# Sheet1.net
KiCad netlist of a schematic drawn in Altium Designer
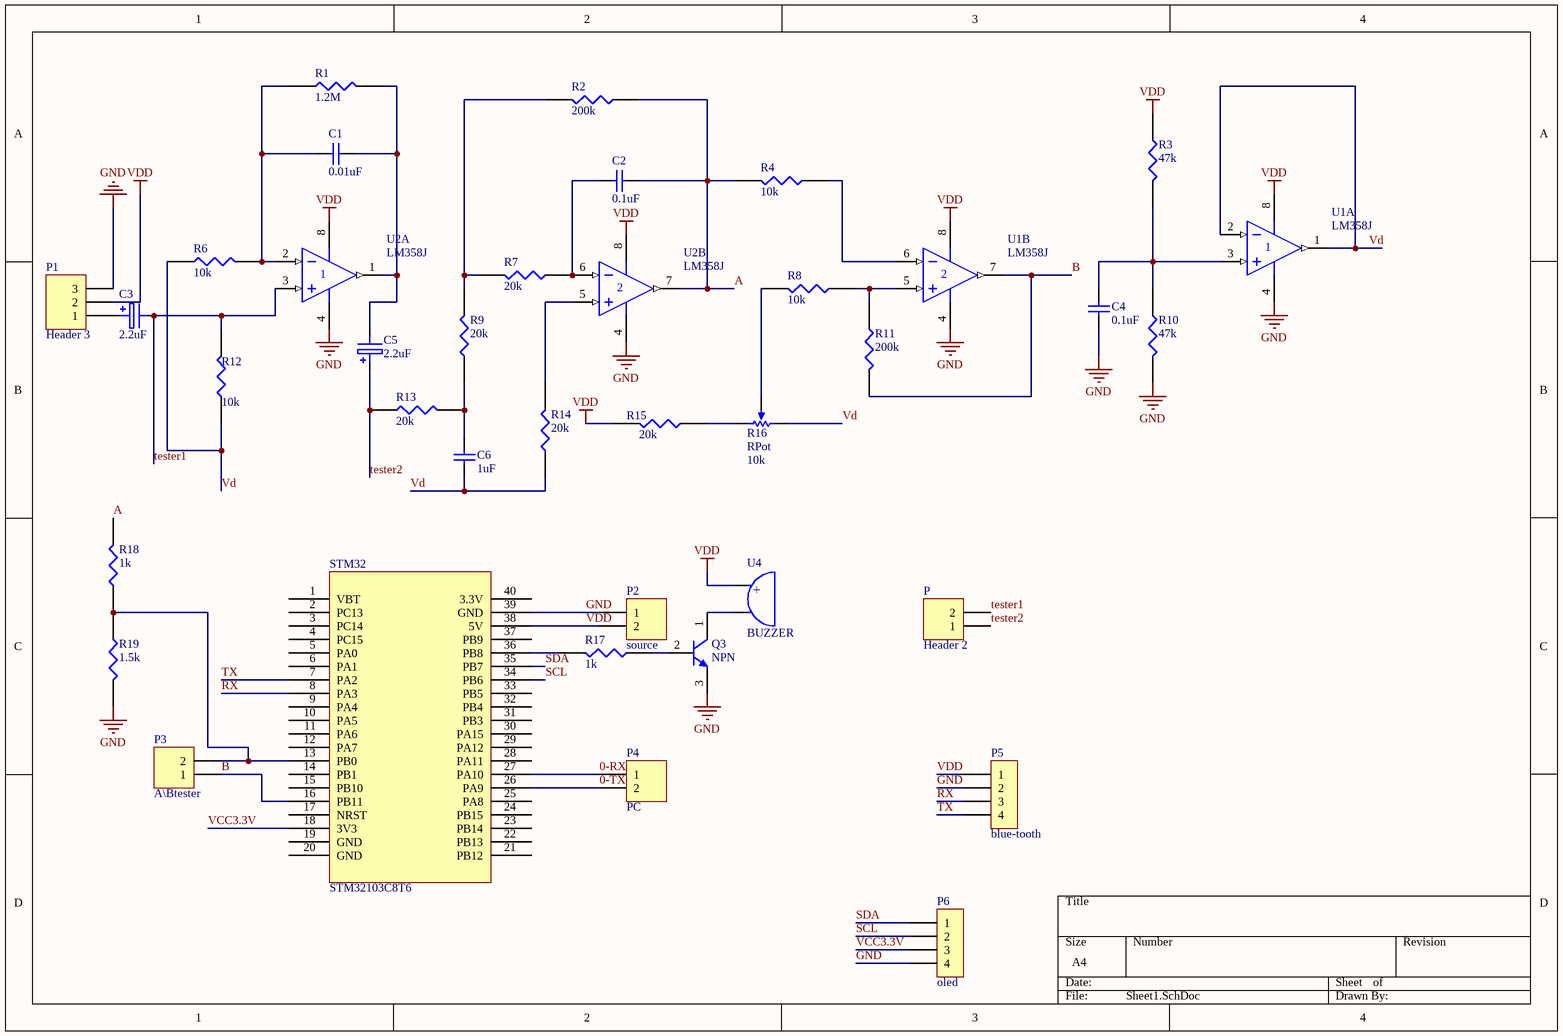
[diagram p0: Sheet1.SchDoc]

(export (version "E")
  (design (tool "Eeschema 10.0.6"))
  (components
    (comp (ref "C1")
      (value "0.01uF")
      (footprint "C2")
      (description "Capacitor")
      (fields (field (name "PUBLISHER") "Altium Limited"))
      (libsource (lib "短学期") (part "Cap"))
    )
    (comp (ref "C2")
      (value "0.1uF")
      (footprint "C2")
      (description "Capacitor")
      (fields (field (name "PUBLISHER") "Altium Limited"))
      (libsource (lib "短学期") (part "Cap"))
    )
    (comp (ref "C3")
      (value "2.2uF")
      (footprint "RB.15/.3")
      (description "电解电容")
      (libsource (lib "Exp20030704") (part "Cap2"))
    )
    (comp (ref "C4")
      (value "0.1uF")
      (footprint "C2")
      (description "Capacitor")
      (fields (field (name "PUBLISHER") "Altium Limited"))
      (libsource (lib "短学期") (part "Cap"))
    )
    (comp (ref "C5")
      (value "2.2uF")
      (footprint "RB.15/.3")
      (description "电解电容")
      (libsource (lib "") (part "Cap2_1"))
    )
    (comp (ref "C6")
      (value "1uF")
      (footprint "C2")
      (description "Capacitor")
      (fields (field (name "PUBLISHER") "Altium Limited"))
      (libsource (lib "短学期") (part "Cap"))
    )
    (comp (ref "P")
      (value "Header 2")
      (footprint "SIP2")
      (description "Header, 2-Pin")
      (fields (field (name "PUBLISHER") "Altium Limited"))
      (libsource (lib "") (part "Header 2_1"))
    )
    (comp (ref "P1")
      (value "Header 3")
      (footprint "SIP3")
      (description "Header, 3-Pin")
      (fields (field (name "PUBLISHER") "Altium Limited"))
      (libsource (lib "短学期") (part "Header 3"))
    )
    (comp (ref "P2")
      (value "source")
      (footprint "SIP2")
      (description "Header, 2-Pin")
      (fields (field (name "PUBLISHER") "Altium Limited"))
      (libsource (lib "Exp20030704") (part "Header 2"))
    )
    (comp (ref "P3")
      (value "~{A}Btester")
      (footprint "SIP2")
      (description "Header, 2-Pin")
      (fields (field (name "PUBLISHER") "Altium Limited"))
      (libsource (lib "") (part "Header 2_1"))
    )
    (comp (ref "P4")
      (value "PC")
      (footprint "SIP2")
      (description "Header, 2-Pin")
      (fields (field (name "PUBLISHER") "Altium Limited"))
      (libsource (lib "Exp20030704") (part "Header 2"))
    )
    (comp (ref "P5")
      (value "blue-tooth")
      (footprint "SIP4")
      (description "Connector")
      (libsource (lib "Exp20030704") (part "Header 4"))
    )
    (comp (ref "P6")
      (value "oled")
      (footprint "SSD1306")
      (description "Connector")
      (libsource (lib "Exp20030704") (part "Header 4"))
    )
    (comp (ref "Q3")
      (value "NPN")
      (footprint "TO-P2")
      (description "NPN Bipolar Transistor")
      (fields (field (name "PUBLISHER") "Altium Limited"))
      (libsource (lib "Exp20030704") (part "NPN"))
    )
    (comp (ref "R1") (value "1.2M") (footprint "AXIAL0.4") (libsource (lib "Exp20030704") (part "RES1")))
    (comp (ref "R2") (value "200k") (footprint "AXIAL0.4") (libsource (lib "Exp20030704") (part "RES1")))
    (comp (ref "R3") (value "47k") (footprint "AXIAL0.4") (libsource (lib "Exp20030704") (part "RES1")))
    (comp (ref "R4") (value "10k") (footprint "AXIAL0.4") (libsource (lib "Exp20030704") (part "RES1")))
    (comp (ref "R6") (value "10k") (footprint "AXIAL0.4") (libsource (lib "Exp20030704") (part "RES1")))
    (comp (ref "R7") (value "20k") (footprint "AXIAL0.4") (libsource (lib "Exp20030704") (part "RES1")))
    (comp (ref "R8") (value "10k") (footprint "AXIAL0.4") (libsource (lib "Exp20030704") (part "RES1")))
    (comp (ref "R9") (value "20k") (footprint "AXIAL0.4") (libsource (lib "Exp20030704") (part "RES1")))
    (comp (ref "R10") (value "47k") (footprint "AXIAL0.4") (libsource (lib "Exp20030704") (part "RES1")))
    (comp (ref "R11") (value "200k") (footprint "AXIAL0.4") (libsource (lib "Exp20030704") (part "RES1")))
    (comp (ref "R12") (value "10k") (footprint "AXIAL0.4") (libsource (lib "Exp20030704") (part "RES1")))
    (comp (ref "R13") (value "20k") (footprint "AXIAL0.4") (libsource (lib "Exp20030704") (part "RES1")))
    (comp (ref "R14") (value "20k") (footprint "AXIAL0.4") (libsource (lib "Exp20030704") (part "RES1")))
    (comp (ref "R15") (value "20k") (footprint "AXIAL0.4") (libsource (lib "Exp20030704") (part "RES1")))
    (comp (ref "R16")
      (value "RPot")
      (footprint "VR5")
      (description "Potentiometer")
      (fields (field (name "ALTIUM_VALUE") "10k") (field (name "PUBLISHER") "Altium Limited"))
      (libsource (lib "Miscellaneous Devices") (part "RPot"))
    )
    (comp (ref "R17") (value "1k") (footprint "AXIAL0.4") (libsource (lib "Exp20030704") (part "RES1")))
    (comp (ref "R18") (value "1k") (footprint "AXIAL0.4") (libsource (lib "Exp20030704") (part "RES1")))
    (comp (ref "R19") (value "1.5k") (footprint "AXIAL0.4") (libsource (lib "Exp20030704") (part "RES1")))
    (comp (ref "STM32")
      (value "STM32103C8T6")
      (footprint "STM32F103C8T6")
      (libsource (lib "Exp20030704") (part "STM32103C8T6"))
    )
    (comp (ref "U1")
      (value "LM358J")
      (footprint "DIP-8")
      (description "Dual Low-Power Operational Amplifier")
      (fields (field (name "PUBLISHER") "Altium Limited"))
      (libsource (lib "Exp20030704") (part "LM358J"))
    )
    (comp (ref "U2")
      (value "LM358J")
      (footprint "DIP-8")
      (description "Dual Low-Power Operational Amplifier")
      (fields (field (name "PUBLISHER") "Altium Limited"))
      (libsource (lib "Exp20030704") (part "LM358J"))
    )
    (comp (ref "U4")
      (value "BUZZER")
      (footprint "Buzzer")
      (description "Buzzer")
      (libsource (lib "Miscellaneous Devices") (part "BUZZER"))
    )
  )
  (nets
    (net (code "1") (name "/0-RX") (class "Default")
      (node (ref "P4") (pin "1") (pinfunction "1_1") (pintype "passive"))
      (node (ref "STM32") (pin "27") (pinfunction "PA10_27") (pintype "passive"))
    )
    (net (code "2") (name "/0-TX") (class "Default")
      (node (ref "P4") (pin "2") (pinfunction "2_2") (pintype "passive"))
      (node (ref "STM32") (pin "26") (pinfunction "PA9_26") (pintype "passive"))
    )
    (net (code "3") (name "/A") (class "Default")
      (node (ref "C2") (pin "2") (pinfunction "2_2") (pintype "passive"))
      (node (ref "R18") (pin "2") (pinfunction "2_2") (pintype "passive"))
      (node (ref "R2") (pin "1") (pinfunction "1_1") (pintype "passive"))
      (node (ref "R4") (pin "2") (pinfunction "2_2") (pintype "passive"))
      (node (ref "U2") (pin "7") (pinfunction "OUT_7") (pintype "output"))
    )
    (net (code "4") (name "/B") (class "Default")
      (node (ref "P3") (pin "1") (pinfunction "1_1") (pintype "passive"))
      (node (ref "R11") (pin "2") (pinfunction "2_2") (pintype "passive"))
      (node (ref "STM32") (pin "16") (pinfunction "PB11_16") (pintype "passive"))
      (node (ref "U1") (pin "7") (pinfunction "OUT_7") (pintype "output"))
    )
    (net (code "5") (name "/RX") (class "Default")
      (node (ref "P5") (pin "3") (pinfunction "3_3") (pintype "passive"))
      (node (ref "STM32") (pin "8") (pinfunction "PA3_8") (pintype "passive"))
    )
    (net (code "6") (name "/SCL") (class "Default")
      (node (ref "P6") (pin "2") (pinfunction "2_2") (pintype "passive"))
      (node (ref "STM32") (pin "34") (pinfunction "PB6_34") (pintype "passive"))
    )
    (net (code "7") (name "/SDA") (class "Default")
      (node (ref "P6") (pin "1") (pinfunction "1_1") (pintype "passive"))
      (node (ref "STM32") (pin "35") (pinfunction "PB7_35") (pintype "passive"))
    )
    (net (code "8") (name "/TX") (class "Default")
      (node (ref "P5") (pin "4") (pinfunction "4_4") (pintype "passive"))
      (node (ref "STM32") (pin "7") (pinfunction "PA2_7") (pintype "passive"))
    )
    (net (code "9") (name "/VCC3.3V") (class "Default")
      (node (ref "P6") (pin "3") (pinfunction "3_3") (pintype "passive"))
      (node (ref "STM32") (pin "18") (pinfunction "3V3_18") (pintype "passive"))
    )
    (net (code "10") (name "/Vd") (class "Default")
      (node (ref "C6") (pin "2") (pinfunction "2_2") (pintype "passive"))
      (node (ref "R12") (pin "1") (pinfunction "1_1") (pintype "passive"))
      (node (ref "R14") (pin "1") (pinfunction "1_1") (pintype "passive"))
      (node (ref "R16") (pin "1") (pinfunction "TOP_1") (pintype "passive"))
      (node (ref "R6") (pin "1") (pinfunction "1_1") (pintype "passive"))
      (node (ref "U1") (pin "1") (pinfunction "OUT_1") (pintype "output"))
      (node (ref "U1") (pin "2") (pinfunction "IN-_2") (pintype "input"))
    )
    (net (code "11") (name "/tester1") (class "Default")
      (node (ref "C3") (pin "2") (pinfunction "2_2") (pintype "passive"))
      (node (ref "P") (pin "2") (pinfunction "2_2") (pintype "passive"))
      (node (ref "R12") (pin "2") (pinfunction "2_2") (pintype "passive"))
      (node (ref "U2") (pin "3") (pinfunction "IN+_3") (pintype "input"))
    )
    (net (code "12") (name "/tester2") (class "Default")
      (node (ref "C5") (pin "2") (pinfunction "2_2") (pintype "passive"))
      (node (ref "P") (pin "1") (pinfunction "1_1") (pintype "passive"))
      (node (ref "R13") (pin "1") (pinfunction "1_1") (pintype "passive"))
    )
    (net (code "13") (name "GND") (class "Default")
      (node (ref "C4") (pin "1") (pinfunction "1_1") (pintype "passive"))
      (node (ref "P1") (pin "3") (pinfunction "3_3") (pintype "passive"))
      (node (ref "P2") (pin "1") (pinfunction "1_1") (pintype "passive"))
      (node (ref "P5") (pin "2") (pinfunction "2_2") (pintype "passive"))
      (node (ref "P6") (pin "4") (pinfunction "4_4") (pintype "passive"))
      (node (ref "Q3") (pin "3") (pinfunction "E_3") (pintype "passive"))
      (node (ref "R10") (pin "2") (pinfunction "2_2") (pintype "passive"))
      (node (ref "R19") (pin "2") (pinfunction "2_2") (pintype "passive"))
      (node (ref "STM32") (pin "39") (pinfunction "GND_39") (pintype "passive"))
      (node (ref "U1") (pin "4") (pinfunction "V-_4") (pintype "power_in"))
      (node (ref "U2") (pin "4") (pinfunction "V-_4") (pintype "power_in"))
    )
    (net (code "14") (name "Net-(C3-Pad1)") (class "Default")
      (node (ref "C3") (pin "1") (pinfunction "1_1") (pintype "passive"))
      (node (ref "P1") (pin "1") (pinfunction "1_1") (pintype "passive"))
    )
    (net (code "15") (name "Net-(C6-Pad1)") (class "Default")
      (node (ref "C6") (pin "1") (pinfunction "1_1") (pintype "passive"))
      (node (ref "R13") (pin "2") (pinfunction "2_2") (pintype "passive"))
      (node (ref "R9") (pin "1") (pinfunction "1_1") (pintype "passive"))
    )
    (net (code "16") (name "Net-(Q3-B)") (class "Default")
      (node (ref "Q3") (pin "2") (pinfunction "B_2") (pintype "passive"))
      (node (ref "R17") (pin "1") (pinfunction "1_1") (pintype "passive"))
    )
    (net (code "17") (name "Net-(Q3-C)") (class "Default")
      (node (ref "Q3") (pin "1") (pinfunction "C_1") (pintype "passive"))
      (node (ref "U4") (pin "2") (pinfunction "B_2") (pintype "passive"))
    )
    (net (code "18") (name "Net-(R2-Pad2)") (class "Default")
      (node (ref "R2") (pin "2") (pinfunction "2_2") (pintype "passive"))
      (node (ref "R7") (pin "2") (pinfunction "2_2") (pintype "passive"))
      (node (ref "R9") (pin "2") (pinfunction "2_2") (pintype "passive"))
    )
    (net (code "19") (name "Net-(R16-BOT)") (class "Default")
      (node (ref "R15") (pin "1") (pinfunction "1_1") (pintype "passive"))
      (node (ref "R16") (pin "2") (pinfunction "BOT_2") (pintype "passive"))
    )
    (net (code "20") (name "Net-(R16-TAP)") (class "Default")
      (node (ref "R16") (pin "3") (pinfunction "TAP_3") (pintype "passive"))
      (node (ref "R8") (pin "2") (pinfunction "2_2") (pintype "passive"))
    )
    (net (code "21") (name "Net-(STM32-PB0)") (class "Default")
      (node (ref "P3") (pin "2") (pinfunction "2_2") (pintype "passive"))
      (node (ref "R18") (pin "1") (pinfunction "1_1") (pintype "passive"))
      (node (ref "R19") (pin "1") (pinfunction "1_1") (pintype "passive"))
      (node (ref "STM32") (pin "13") (pinfunction "PB0_13") (pintype "passive"))
    )
    (net (code "22") (name "Net-(STM32-PB8)") (class "Default")
      (node (ref "R17") (pin "2") (pinfunction "2_2") (pintype "passive"))
      (node (ref "STM32") (pin "36") (pinfunction "PB8_36") (pintype "passive"))
    )
    (net (code "23") (name "Net-(U1A-IN+)") (class "Default")
      (node (ref "C4") (pin "2") (pinfunction "2_2") (pintype "passive"))
      (node (ref "R10") (pin "1") (pinfunction "1_1") (pintype "passive"))
      (node (ref "R3") (pin "2") (pinfunction "2_2") (pintype "passive"))
      (node (ref "U1") (pin "3") (pinfunction "IN+_3") (pintype "input"))
    )
    (net (code "24") (name "Net-(U1B-IN+)") (class "Default")
      (node (ref "R11") (pin "1") (pinfunction "1_1") (pintype "passive"))
      (node (ref "R8") (pin "1") (pinfunction "1_1") (pintype "passive"))
      (node (ref "U1") (pin "5") (pinfunction "IN+_5") (pintype "input"))
    )
    (net (code "25") (name "Net-(U1B-IN-)") (class "Default")
      (node (ref "R4") (pin "1") (pinfunction "1_1") (pintype "passive"))
      (node (ref "U1") (pin "6") (pinfunction "IN-_6") (pintype "input"))
    )
    (net (code "26") (name "Net-(U2A-IN-)") (class "Default")
      (node (ref "C1") (pin "1") (pinfunction "1_1") (pintype "passive"))
      (node (ref "R1") (pin "1") (pinfunction "1_1") (pintype "passive"))
      (node (ref "R6") (pin "2") (pinfunction "2_2") (pintype "passive"))
      (node (ref "U2") (pin "2") (pinfunction "IN-_2") (pintype "input"))
    )
    (net (code "27") (name "Net-(U2A-OUT)") (class "Default")
      (node (ref "C1") (pin "2") (pinfunction "2_2") (pintype "passive"))
      (node (ref "C5") (pin "1") (pinfunction "1_1") (pintype "passive"))
      (node (ref "R1") (pin "2") (pinfunction "2_2") (pintype "passive"))
      (node (ref "U2") (pin "1") (pinfunction "OUT_1") (pintype "output"))
    )
    (net (code "28") (name "Net-(U2B-IN+)") (class "Default")
      (node (ref "R14") (pin "2") (pinfunction "2_2") (pintype "passive"))
      (node (ref "U2") (pin "5") (pinfunction "IN+_5") (pintype "input"))
    )
    (net (code "29") (name "Net-(U2B-IN-)") (class "Default")
      (node (ref "C2") (pin "1") (pinfunction "1_1") (pintype "passive"))
      (node (ref "R7") (pin "1") (pinfunction "1_1") (pintype "passive"))
      (node (ref "U2") (pin "6") (pinfunction "IN-_6") (pintype "input"))
    )
    (net (code "30") (name "VDD") (class "Default")
      (node (ref "P1") (pin "2") (pinfunction "2_2") (pintype "passive"))
      (node (ref "P2") (pin "2") (pinfunction "2_2") (pintype "passive"))
      (node (ref "P5") (pin "1") (pinfunction "1_1") (pintype "passive"))
      (node (ref "R15") (pin "2") (pinfunction "2_2") (pintype "passive"))
      (node (ref "R3") (pin "1") (pinfunction "1_1") (pintype "passive"))
      (node (ref "STM32") (pin "38") (pinfunction "5V_38") (pintype "passive"))
      (node (ref "U1") (pin "8") (pinfunction "V+_8") (pintype "power_in"))
      (node (ref "U2") (pin "8") (pinfunction "V+_8") (pintype "power_in"))
      (node (ref "U4") (pin "1") (pinfunction "A_1") (pintype "passive"))
    )
    (net (code "31") (name "unconnected-(STM32-3.3V-Pad40)") (class "Default")
      (node (ref "STM32") (pin "40") (pinfunction "3.3V_40") (pintype "passive"))
    )
    (net (code "32") (name "unconnected-(STM32-GND-Pad19)") (class "Default")
      (node (ref "STM32") (pin "19") (pinfunction "GND_19") (pintype "passive"))
    )
    (net (code "33") (name "unconnected-(STM32-GND-Pad20)") (class "Default")
      (node (ref "STM32") (pin "20") (pinfunction "GND_20") (pintype "passive"))
    )
    (net (code "34") (name "unconnected-(STM32-NRST-Pad17)") (class "Default")
      (node (ref "STM32") (pin "17") (pinfunction "NRST_17") (pintype "passive"))
    )
    (net (code "35") (name "unconnected-(STM32-PA0-Pad5)") (class "Default")
      (node (ref "STM32") (pin "5") (pinfunction "PA0_5") (pintype "passive"))
    )
    (net (code "36") (name "unconnected-(STM32-PA1-Pad6)") (class "Default")
      (node (ref "STM32") (pin "6") (pinfunction "PA1_6") (pintype "passive"))
    )
    (net (code "37") (name "unconnected-(STM32-PA4-Pad9)") (class "Default")
      (node (ref "STM32") (pin "9") (pinfunction "PA4_9") (pintype "passive"))
    )
    (net (code "38") (name "unconnected-(STM32-PA5-Pad10)") (class "Default")
      (node (ref "STM32") (pin "10") (pinfunction "PA5_10") (pintype "passive"))
    )
    (net (code "39") (name "unconnected-(STM32-PA6-Pad11)") (class "Default")
      (node (ref "STM32") (pin "11") (pinfunction "PA6_11") (pintype "passive"))
    )
    (net (code "40") (name "unconnected-(STM32-PA7-Pad12)") (class "Default")
      (node (ref "STM32") (pin "12") (pinfunction "PA7_12") (pintype "passive"))
    )
    (net (code "41") (name "unconnected-(STM32-PA8-Pad25)") (class "Default")
      (node (ref "STM32") (pin "25") (pinfunction "PA8_25") (pintype "passive"))
    )
    (net (code "42") (name "unconnected-(STM32-PA11-Pad28)") (class "Default")
      (node (ref "STM32") (pin "28") (pinfunction "PA11_28") (pintype "passive"))
    )
    (net (code "43") (name "unconnected-(STM32-PA12-Pad29)") (class "Default")
      (node (ref "STM32") (pin "29") (pinfunction "PA12_29") (pintype "passive"))
    )
    (net (code "44") (name "unconnected-(STM32-PA15-Pad30)") (class "Default")
      (node (ref "STM32") (pin "30") (pinfunction "PA15_30") (pintype "passive"))
    )
    (net (code "45") (name "unconnected-(STM32-PB1-Pad14)") (class "Default")
      (node (ref "STM32") (pin "14") (pinfunction "PB1_14") (pintype "passive"))
    )
    (net (code "46") (name "unconnected-(STM32-PB3-Pad31)") (class "Default")
      (node (ref "STM32") (pin "31") (pinfunction "PB3_31") (pintype "passive"))
    )
    (net (code "47") (name "unconnected-(STM32-PB4-Pad32)") (class "Default")
      (node (ref "STM32") (pin "32") (pinfunction "PB4_32") (pintype "passive"))
    )
    (net (code "48") (name "unconnected-(STM32-PB5-Pad33)") (class "Default")
      (node (ref "STM32") (pin "33") (pinfunction "PB5_33") (pintype "passive"))
    )
    (net (code "49") (name "unconnected-(STM32-PB9-Pad37)") (class "Default")
      (node (ref "STM32") (pin "37") (pinfunction "PB9_37") (pintype "passive"))
    )
    (net (code "50") (name "unconnected-(STM32-PB10-Pad15)") (class "Default")
      (node (ref "STM32") (pin "15") (pinfunction "PB10_15") (pintype "passive"))
    )
    (net (code "51") (name "unconnected-(STM32-PB12-Pad21)") (class "Default")
      (node (ref "STM32") (pin "21") (pinfunction "PB12_21") (pintype "passive"))
    )
    (net (code "52") (name "unconnected-(STM32-PB13-Pad22)") (class "Default")
      (node (ref "STM32") (pin "22") (pinfunction "PB13_22") (pintype "passive"))
    )
    (net (code "53") (name "unconnected-(STM32-PB14-Pad23)") (class "Default")
      (node (ref "STM32") (pin "23") (pinfunction "PB14_23") (pintype "passive"))
    )
    (net (code "54") (name "unconnected-(STM32-PB15-Pad24)") (class "Default")
      (node (ref "STM32") (pin "24") (pinfunction "PB15_24") (pintype "passive"))
    )
    (net (code "55") (name "unconnected-(STM32-PC13-Pad2)") (class "Default")
      (node (ref "STM32") (pin "2") (pinfunction "PC13_2") (pintype "passive"))
    )
    (net (code "56") (name "unconnected-(STM32-PC14-Pad3)") (class "Default")
      (node (ref "STM32") (pin "3") (pinfunction "PC14_3") (pintype "passive"))
    )
    (net (code "57") (name "unconnected-(STM32-PC15-Pad4)") (class "Default")
      (node (ref "STM32") (pin "4") (pinfunction "PC15_4") (pintype "passive"))
    )
    (net (code "58") (name "unconnected-(STM32-VBT-Pad1)") (class "Default")
      (node (ref "STM32") (pin "1") (pinfunction "VBT_1") (pintype "passive"))
    )
  )
)
